# EGR_326_ATmega328P_Board.net
KiCad netlist of a schematic drawn in EAGLE
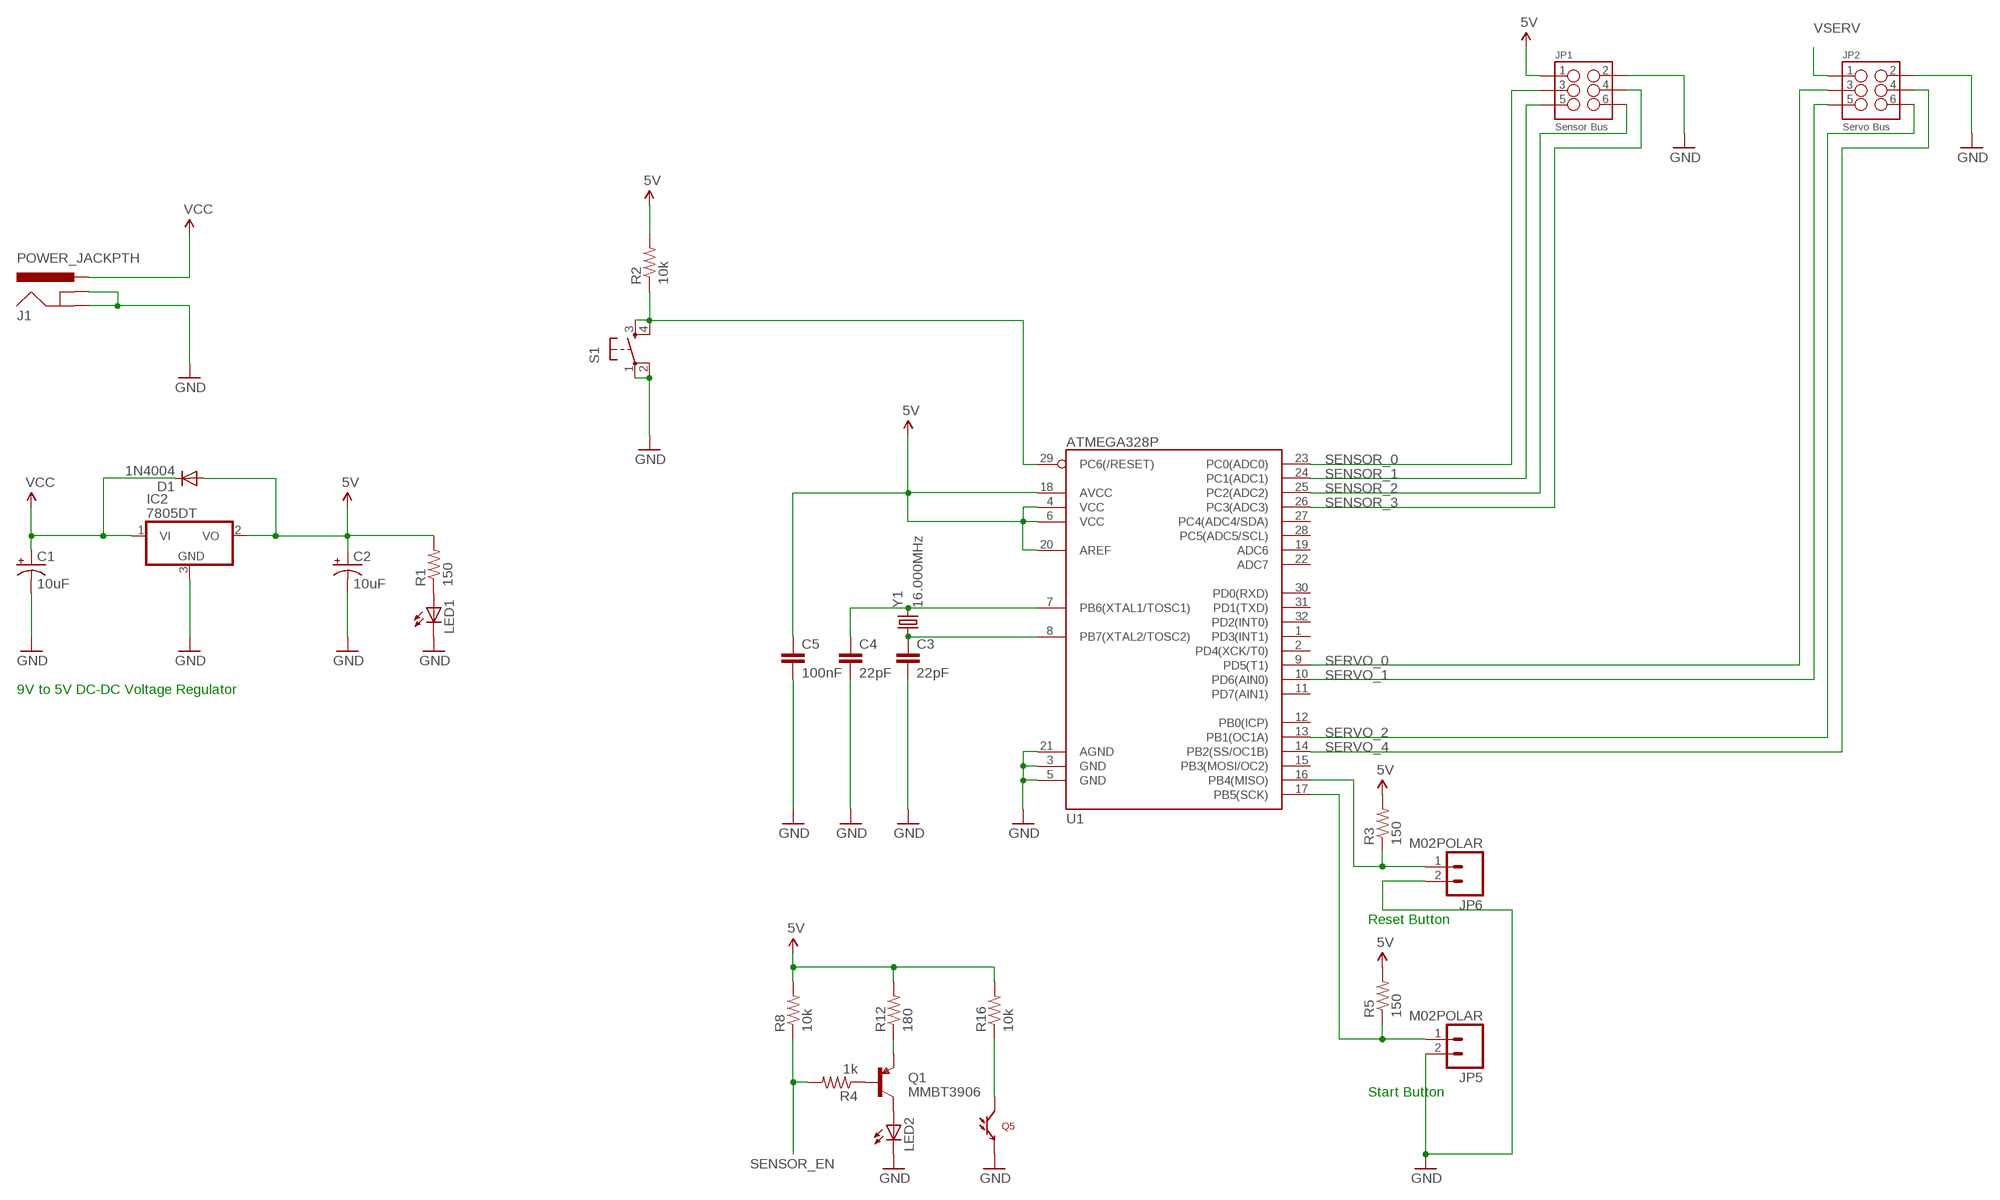
[diagram p0: schematic, sheet 1]

(export (version "E")
  (design (tool "Eeschema 10.0.6"))
  (components
    (comp (ref "C1")
      (value "10uF")
      (footprint "eagle-import:PANASONIC_D")
      (libsource (lib "eagle-import") (part "CAP_POLD"))
    )
    (comp (ref "C2")
      (value "10uF")
      (footprint "eagle-import:PANASONIC_D")
      (libsource (lib "eagle-import") (part "CAP_POLD"))
    )
    (comp (ref "C3")
      (value "22pF")
      (footprint "eagle-import:0603-CAP")
      (libsource (lib "eagle-import") (part "22PF-50V-5%(0603)"))
    )
    (comp (ref "C4")
      (value "22pF")
      (footprint "eagle-import:0603-CAP")
      (libsource (lib "eagle-import") (part "22PF-50V-5%(0603)"))
    )
    (comp (ref "C5")
      (value "100nF")
      (footprint "eagle-import:0603-CAP")
      (libsource (lib "eagle-import") (part "22PF-50V-5%(0603)"))
    )
    (comp (ref "D1")
      (value "1N4004")
      (footprint "eagle-import:DO41-10")
      (libsource (lib "eagle-import") (part "1N4004"))
    )
    (comp (ref "IC2")
      (value "7805DT")
      (footprint "eagle-import:TO252")
      (libsource (lib "eagle-import") (part "78DT05"))
    )
    (comp (ref "J1")
      (value "POWER_JACKPTH")
      (footprint "eagle-import:POWER_JACK_PTH")
      (libsource (lib "eagle-import") (part "POWER_JACKPTH"))
    )
    (comp (ref "JP1")
      (value "Sensor Bus")
      (footprint "eagle-import:2X3-SHROUDED")
      (libsource (lib "eagle-import") (part "M03X2"))
    )
    (comp (ref "JP2")
      (value "Servo Bus")
      (footprint "eagle-import:2X3-SHROUDED")
      (libsource (lib "eagle-import") (part "M03X2"))
    )
    (comp (ref "JP5")
      (value "M02POLAR")
      (footprint "eagle-import:MOLEX-1X2")
      (libsource (lib "eagle-import") (part "M02POLAR"))
    )
    (comp (ref "JP6")
      (value "M02POLAR")
      (footprint "eagle-import:MOLEX-1X2")
      (libsource (lib "eagle-import") (part "M02POLAR"))
    )
    (comp (ref "LED1")
      (value "LED1206")
      (footprint "eagle-import:LED-1206")
      (libsource (lib "eagle-import") (part "LED1206"))
    )
    (comp (ref "LED2")
      (value "LED3MM")
      (footprint "eagle-import:LED3MM")
      (libsource (lib "eagle-import") (part "LED3MM"))
    )
    (comp (ref "Q1")
      (value "MMBT3906")
      (footprint "eagle-import:SOT23")
      (libsource (lib "eagle-import") (part "TRANSISTOR_PNPMMBT3906"))
    )
    (comp (ref "Q5")
      (value "LTR-301")
      (footprint "eagle-import:LTR-301")
      (libsource (lib "eagle-import") (part "LTR-301"))
    )
    (comp (ref "R1")
      (value "150")
      (footprint "eagle-import:0603-RES")
      (libsource (lib "eagle-import") (part "RESISTOR0603"))
    )
    (comp (ref "R2")
      (value "10k")
      (footprint "eagle-import:0603-RES")
      (libsource (lib "eagle-import") (part "RESISTOR0603"))
    )
    (comp (ref "R3")
      (value "150")
      (footprint "eagle-import:0603-RES")
      (libsource (lib "eagle-import") (part "RESISTOR0603"))
    )
    (comp (ref "R4")
      (value "1k")
      (footprint "eagle-import:0603-RES")
      (libsource (lib "eagle-import") (part "RESISTOR0603"))
    )
    (comp (ref "R5")
      (value "150")
      (footprint "eagle-import:0603-RES")
      (libsource (lib "eagle-import") (part "RESISTOR0603"))
    )
    (comp (ref "R8")
      (value "10k")
      (footprint "eagle-import:0603-RES")
      (libsource (lib "eagle-import") (part "RESISTOR0603"))
    )
    (comp (ref "R12")
      (value "180")
      (footprint "eagle-import:0603-RES")
      (libsource (lib "eagle-import") (part "RESISTOR0603"))
    )
    (comp (ref "R16")
      (value "10k")
      (footprint "eagle-import:0603-RES")
      (libsource (lib "eagle-import") (part "RESISTOR0603"))
    )
    (comp (ref "S1")
      (value "TAC_SWITCHSMD")
      (footprint "eagle-import:TACTILE_SWITCH_SMD")
      (libsource (lib "eagle-import") (part "TAC_SWITCHSMD"))
    )
    (comp (ref "U1")
      (value "ATMEGA328P")
      (footprint "eagle-import:TQFP32-08")
      (libsource (lib "eagle-import") (part "ATMEGA328_SMT"))
    )
    (comp (ref "Y1")
      (value "16.000MHz")
      (footprint "eagle-import:HC49UP")
      (libsource (lib "eagle-import") (part "CRYSTALSMD"))
    )
  )
  (nets
    (net (code "1") (name "/SENSOR_0") (class "Default")
      (node (ref "JP1") (pin "3") (pinfunction "3_3") (pintype "bidirectional"))
      (node (ref "U1") (pin "23") (pinfunction "PC0(ADC0)_23") (pintype "bidirectional"))
    )
    (net (code "2") (name "/SENSOR_1") (class "Default")
      (node (ref "JP1") (pin "5") (pinfunction "5_5") (pintype "bidirectional"))
      (node (ref "U1") (pin "24") (pinfunction "PC1(ADC1)_24") (pintype "bidirectional"))
    )
    (net (code "3") (name "/SENSOR_2") (class "Default")
      (node (ref "JP1") (pin "6") (pinfunction "6_6") (pintype "bidirectional"))
      (node (ref "U1") (pin "25") (pinfunction "PC2(ADC2)_25") (pintype "bidirectional"))
    )
    (net (code "4") (name "/SENSOR_3") (class "Default")
      (node (ref "JP1") (pin "4") (pinfunction "4_4") (pintype "bidirectional"))
      (node (ref "U1") (pin "26") (pinfunction "PC3(ADC3)_26") (pintype "bidirectional"))
    )
    (net (code "5") (name "/SENSOR_EN") (class "Default")
      (node (ref "R4") (pin "2") (pinfunction "2_2") (pintype "passive"))
      (node (ref "R8") (pin "1") (pinfunction "1_1") (pintype "passive"))
    )
    (net (code "6") (name "/SERVO_0") (class "Default")
      (node (ref "JP2") (pin "3") (pinfunction "3_3") (pintype "bidirectional"))
      (node (ref "U1") (pin "9") (pinfunction "PD5(T1)_9") (pintype "bidirectional"))
    )
    (net (code "7") (name "/SERVO_1") (class "Default")
      (node (ref "JP2") (pin "5") (pinfunction "5_5") (pintype "bidirectional"))
      (node (ref "U1") (pin "10") (pinfunction "PD6(AIN0)_10") (pintype "bidirectional"))
    )
    (net (code "8") (name "/SERVO_2") (class "Default")
      (node (ref "JP2") (pin "6") (pinfunction "6_6") (pintype "bidirectional"))
      (node (ref "U1") (pin "13") (pinfunction "PB1(OC1A)_13") (pintype "bidirectional"))
    )
    (net (code "9") (name "/SERVO_4") (class "Default")
      (node (ref "JP2") (pin "4") (pinfunction "4_4") (pintype "bidirectional"))
      (node (ref "U1") (pin "14") (pinfunction "PB2(SS/OC1B)_14") (pintype "bidirectional"))
    )
    (net (code "10") (name "/VSERV") (class "Default")
      (node (ref "JP2") (pin "1") (pinfunction "1_1") (pintype "bidirectional"))
    )
    (net (code "11") (name "5V") (class "Default")
      (node (ref "C2") (pin "+") (pinfunction "+_+") (pintype "passive"))
      (node (ref "C5") (pin "1") (pinfunction "1_1") (pintype "passive"))
      (node (ref "D1") (pin "A") (pinfunction "A_A") (pintype "passive"))
      (node (ref "IC2") (pin "2") (pinfunction "VO_2") (pintype "passive"))
      (node (ref "JP1") (pin "1") (pinfunction "1_1") (pintype "bidirectional"))
      (node (ref "R1") (pin "2") (pinfunction "2_2") (pintype "passive"))
      (node (ref "R12") (pin "2") (pinfunction "2_2") (pintype "passive"))
      (node (ref "R16") (pin "2") (pinfunction "2_2") (pintype "passive"))
      (node (ref "R2") (pin "2") (pinfunction "2_2") (pintype "passive"))
      (node (ref "R3") (pin "2") (pinfunction "2_2") (pintype "passive"))
      (node (ref "R5") (pin "2") (pinfunction "2_2") (pintype "passive"))
      (node (ref "R8") (pin "2") (pinfunction "2_2") (pintype "passive"))
      (node (ref "U1") (pin "18") (pinfunction "AVCC_18") (pintype "bidirectional"))
      (node (ref "U1") (pin "20") (pinfunction "AREF_20") (pintype "bidirectional"))
      (node (ref "U1") (pin "4") (pinfunction "VCC_4") (pintype "bidirectional"))
      (node (ref "U1") (pin "6") (pinfunction "VCC_6") (pintype "bidirectional"))
    )
    (net (code "12") (name "GND") (class "Default")
      (node (ref "C1") (pin "-") (pinfunction "-_-") (pintype "passive"))
      (node (ref "C2") (pin "-") (pinfunction "-_-") (pintype "passive"))
      (node (ref "C3") (pin "2") (pinfunction "2_2") (pintype "passive"))
      (node (ref "C4") (pin "2") (pinfunction "2_2") (pintype "passive"))
      (node (ref "C5") (pin "2") (pinfunction "2_2") (pintype "passive"))
      (node (ref "IC2") (pin "3") (pinfunction "GND_3") (pintype "passive"))
      (node (ref "J1") (pin "GND") (pinfunction "GND_GND") (pintype "bidirectional"))
      (node (ref "J1") (pin "GNDBREAK") (pinfunction "GNDBREAK_GNDBREAK") (pintype "bidirectional"))
      (node (ref "JP1") (pin "2") (pinfunction "2_2") (pintype "bidirectional"))
      (node (ref "JP2") (pin "2") (pinfunction "2_2") (pintype "bidirectional"))
      (node (ref "JP5") (pin "2") (pinfunction "2_2") (pintype "passive"))
      (node (ref "JP6") (pin "2") (pinfunction "2_2") (pintype "passive"))
      (node (ref "LED1") (pin "C") (pinfunction "C_C") (pintype "passive"))
      (node (ref "LED2") (pin "K") (pinfunction "C_K") (pintype "passive"))
      (node (ref "Q5") (pin "E") (pinfunction "E_E") (pintype "bidirectional"))
      (node (ref "S1") (pin "1") (pinfunction "1_1") (pintype "passive"))
      (node (ref "S1") (pin "2") (pinfunction "2_2") (pintype "passive"))
      (node (ref "U1") (pin "21") (pinfunction "AGND_21") (pintype "bidirectional"))
      (node (ref "U1") (pin "3") (pinfunction "GND_3") (pintype "bidirectional"))
      (node (ref "U1") (pin "5") (pinfunction "GND_5") (pintype "bidirectional"))
    )
    (net (code "13") (name "Net-(LED1-PadA)") (class "Default")
      (node (ref "LED1") (pin "A") (pinfunction "A_A") (pintype "passive"))
      (node (ref "R1") (pin "1") (pinfunction "1_1") (pintype "passive"))
    )
    (net (code "14") (name "Net-(Q1-B)") (class "Default")
      (node (ref "Q1") (pin "1") (pinfunction "B_1") (pintype "passive"))
      (node (ref "R4") (pin "1") (pinfunction "1_1") (pintype "passive"))
    )
    (net (code "15") (name "Net-(Q1-C)") (class "Default")
      (node (ref "LED2") (pin "A") (pinfunction "A_A") (pintype "passive"))
      (node (ref "Q1") (pin "3") (pinfunction "C_3") (pintype "passive"))
    )
    (net (code "16") (name "Net-(Q1-E)") (class "Default")
      (node (ref "Q1") (pin "2") (pinfunction "E_2") (pintype "passive"))
      (node (ref "R12") (pin "1") (pinfunction "1_1") (pintype "passive"))
    )
    (net (code "17") (name "Net-(Q5-PadC)") (class "Default")
      (node (ref "Q5") (pin "C") (pinfunction "C_C") (pintype "bidirectional"))
      (node (ref "R16") (pin "1") (pinfunction "1_1") (pintype "passive"))
    )
    (net (code "18") (name "Net-(U1-PB4(MISO))") (class "Default")
      (node (ref "JP6") (pin "1") (pinfunction "1_1") (pintype "passive"))
      (node (ref "R3") (pin "1") (pinfunction "1_1") (pintype "passive"))
      (node (ref "U1") (pin "16") (pinfunction "PB4(MISO)_16") (pintype "bidirectional"))
    )
    (net (code "19") (name "Net-(U1-PB5(SCK))") (class "Default")
      (node (ref "JP5") (pin "1") (pinfunction "1_1") (pintype "passive"))
      (node (ref "R5") (pin "1") (pinfunction "1_1") (pintype "passive"))
      (node (ref "U1") (pin "17") (pinfunction "PB5(SCK)_17") (pintype "bidirectional"))
    )
    (net (code "20") (name "Net-(U1-PB6(XTAL1{slash}TOSC1))") (class "Default")
      (node (ref "C4") (pin "1") (pinfunction "1_1") (pintype "passive"))
      (node (ref "U1") (pin "7") (pinfunction "PB6(XTAL1/TOSC1)_7") (pintype "bidirectional"))
      (node (ref "Y1") (pin "2") (pinfunction "2_2") (pintype "passive"))
    )
    (net (code "21") (name "Net-(U1-PB7(XTAL2{slash}TOSC2))") (class "Default")
      (node (ref "C3") (pin "1") (pinfunction "1_1") (pintype "passive"))
      (node (ref "U1") (pin "8") (pinfunction "PB7(XTAL2/TOSC2)_8") (pintype "bidirectional"))
      (node (ref "Y1") (pin "1") (pinfunction "1_1") (pintype "passive"))
    )
    (net (code "22") (name "Net-(U1-PC6({slash}RESET))") (class "Default")
      (node (ref "R2") (pin "1") (pinfunction "1_1") (pintype "passive"))
      (node (ref "S1") (pin "3") (pinfunction "3_3") (pintype "passive"))
      (node (ref "S1") (pin "4") (pinfunction "4_4") (pintype "passive"))
      (node (ref "U1") (pin "29") (pinfunction "PC6(/RESET)_29") (pintype "bidirectional"))
    )
    (net (code "23") (name "VCC") (class "Default")
      (node (ref "C1") (pin "+") (pinfunction "+_+") (pintype "passive"))
      (node (ref "D1") (pin "C") (pinfunction "C_C") (pintype "passive"))
      (node (ref "IC2") (pin "1") (pinfunction "VI_1") (pintype "input"))
      (node (ref "J1") (pin "PWR") (pinfunction "PWR_PWR") (pintype "bidirectional"))
    )
    (net (code "24") (name "unconnected-(U1-ADC6-Pad19)") (class "Default")
      (node (ref "U1") (pin "19") (pinfunction "ADC6_19") (pintype "bidirectional"))
    )
    (net (code "25") (name "unconnected-(U1-ADC7-Pad22)") (class "Default")
      (node (ref "U1") (pin "22") (pinfunction "ADC7_22") (pintype "bidirectional"))
    )
    (net (code "26") (name "unconnected-(U1-PB0(ICP)-Pad12)") (class "Default")
      (node (ref "U1") (pin "12") (pinfunction "PB0(ICP)_12") (pintype "bidirectional"))
    )
    (net (code "27") (name "unconnected-(U1-PB3(MOSI{slash}OC2)-Pad15)") (class "Default")
      (node (ref "U1") (pin "15") (pinfunction "PB3(MOSI/OC2)_15") (pintype "bidirectional"))
    )
    (net (code "28") (name "unconnected-(U1-PC4(ADC4{slash}SDA)-Pad27)") (class "Default")
      (node (ref "U1") (pin "27") (pinfunction "PC4(ADC4/SDA)_27") (pintype "bidirectional"))
    )
    (net (code "29") (name "unconnected-(U1-PC5(ADC5{slash}SCL)-Pad28)") (class "Default")
      (node (ref "U1") (pin "28") (pinfunction "PC5(ADC5/SCL)_28") (pintype "bidirectional"))
    )
    (net (code "30") (name "unconnected-(U1-PD0(RXD)-Pad30)") (class "Default")
      (node (ref "U1") (pin "30") (pinfunction "PD0(RXD)_30") (pintype "bidirectional"))
    )
    (net (code "31") (name "unconnected-(U1-PD1(TXD)-Pad31)") (class "Default")
      (node (ref "U1") (pin "31") (pinfunction "PD1(TXD)_31") (pintype "bidirectional"))
    )
    (net (code "32") (name "unconnected-(U1-PD2(INT0)-Pad32)") (class "Default")
      (node (ref "U1") (pin "32") (pinfunction "PD2(INT0)_32") (pintype "bidirectional"))
    )
    (net (code "33") (name "unconnected-(U1-PD3(INT1)-Pad1)") (class "Default")
      (node (ref "U1") (pin "1") (pinfunction "PD3(INT1)_1") (pintype "bidirectional"))
    )
    (net (code "34") (name "unconnected-(U1-PD4(XCK{slash}T0)-Pad2)") (class "Default")
      (node (ref "U1") (pin "2") (pinfunction "PD4(XCK/T0)_2") (pintype "bidirectional"))
    )
    (net (code "35") (name "unconnected-(U1-PD7(AIN1)-Pad11)") (class "Default")
      (node (ref "U1") (pin "11") (pinfunction "PD7(AIN1)_11") (pintype "bidirectional"))
    )
  )
)
